# mcu_board.net
KiCad netlist of a schematic drawn in EAGLE
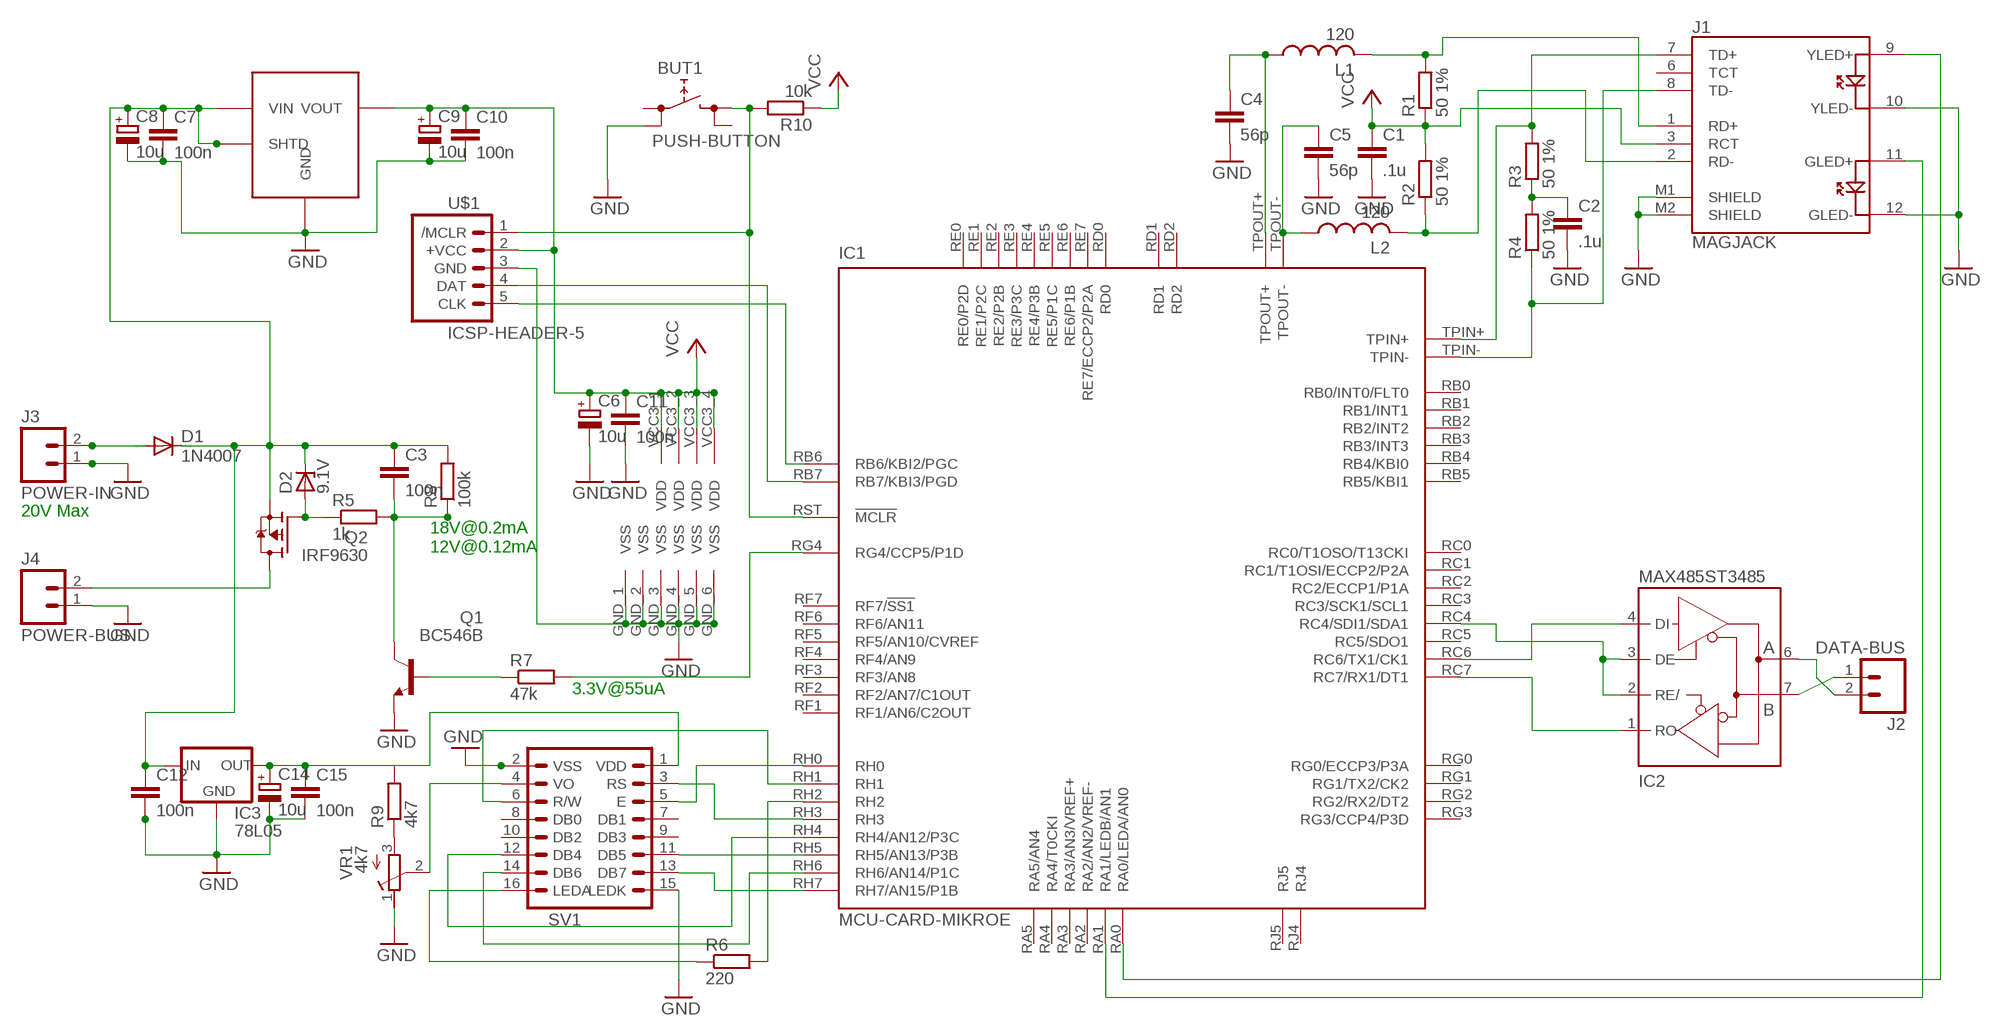
[diagram p0: schematic, sheet 1]

(export (version "E")
  (design (tool "Eeschema 10.0.6"))
  (components
    (comp (ref "BUT1")
      (value "PUSH-BUTTON")
      (footprint "eagle-import:MICRO-SWITCH")
      (libsource (lib "eagle-import") (part "PUSH-BUTTON"))
    )
    (comp (ref "C1")
      (value ".1u")
      (footprint "eagle-import:C050-025X075")
      (libsource (lib "eagle-import") (part "C-EU050-025X075"))
    )
    (comp (ref "C2")
      (value ".1u")
      (footprint "eagle-import:C050-025X075")
      (libsource (lib "eagle-import") (part "C-EU050-025X075"))
    )
    (comp (ref "C3")
      (value "100n")
      (footprint "eagle-import:C050-025X075")
      (libsource (lib "eagle-import") (part "C-EU050-025X075"))
    )
    (comp (ref "C4")
      (value "56p")
      (footprint "eagle-import:C0805")
      (libsource (lib "eagle-import") (part "C-EUC0805"))
    )
    (comp (ref "C5")
      (value "56p")
      (footprint "eagle-import:C0805")
      (libsource (lib "eagle-import") (part "C-EUC0805"))
    )
    (comp (ref "C6")
      (value "10u")
      (footprint "eagle-import:E2,5-6")
      (libsource (lib "eagle-import") (part "CPOL-EUE2.5-6"))
    )
    (comp (ref "C7")
      (value "100n")
      (footprint "eagle-import:C050-025X075")
      (libsource (lib "eagle-import") (part "C-EU050-025X075"))
    )
    (comp (ref "C8")
      (value "10u")
      (footprint "eagle-import:E2,5-7")
      (libsource (lib "eagle-import") (part "CPOL-EUE2.5-7"))
    )
    (comp (ref "C9")
      (value "10u")
      (footprint "eagle-import:E2,5-7")
      (libsource (lib "eagle-import") (part "CPOL-EUE2.5-7"))
    )
    (comp (ref "C10")
      (value "100n")
      (footprint "eagle-import:C050-025X075")
      (libsource (lib "eagle-import") (part "C-EU050-025X075"))
    )
    (comp (ref "C11")
      (value "100n")
      (footprint "eagle-import:C050-025X075")
      (libsource (lib "eagle-import") (part "C-EU050-025X075"))
    )
    (comp (ref "C12")
      (value "100n")
      (footprint "eagle-import:C050-025X075")
      (libsource (lib "eagle-import") (part "C-EU050-025X075"))
    )
    (comp (ref "C14")
      (value "10u")
      (footprint "eagle-import:E2,5-7")
      (libsource (lib "eagle-import") (part "CPOL-EUE2.5-7"))
    )
    (comp (ref "C15")
      (value "100n")
      (footprint "eagle-import:C050-025X075")
      (libsource (lib "eagle-import") (part "C-EU050-025X075"))
    )
    (comp (ref "D1")
      (value "1N4007")
      (footprint "eagle-import:DO41-10")
      (libsource (lib "eagle-import") (part "1N4007"))
    )
    (comp (ref "D2")
      (value "9.1V")
      (footprint "eagle-import:D-5")
      (libsource (lib "eagle-import") (part "ZENERD5"))
    )
    (comp (ref "IC1")
      (value "MCU-CARD-MIKROE")
      (footprint "eagle-import:LV18F")
      (libsource (lib "eagle-import") (part "MCU-CARD-MIKROE"))
    )
    (comp (ref "IC2")
      (value "MAX485ST3485")
      (footprint "eagle-import:SO08")
      (libsource (lib "eagle-import") (part "MAX485ST3485"))
    )
    (comp (ref "IC3")
      (value "78L05")
      (footprint "eagle-import:78LXX")
      (libsource (lib "eagle-import") (part "78LXX"))
    )
    (comp (ref "J1")
      (value "MAGJACK")
      (footprint "eagle-import:MAGJACK")
      (libsource (lib "eagle-import") (part "MAGJACK"))
    )
    (comp (ref "J2")
      (value "DATA-BUS")
      (footprint "eagle-import:SCREWTERMINAL-3.5MM-2")
      (libsource (lib "eagle-import") (part "M02-SCREW-3.5MM3.5MM"))
    )
    (comp (ref "J3")
      (value "POWER-IN")
      (footprint "eagle-import:SCREWTERMINAL-3.5MM-2")
      (libsource (lib "eagle-import") (part "M02-SCREW-3.5MM3.5MM"))
    )
    (comp (ref "J4")
      (value "POWER-BUS")
      (footprint "eagle-import:SCREWTERMINAL-3.5MM-2")
      (libsource (lib "eagle-import") (part "M02-SCREW-3.5MM3.5MM"))
    )
    (comp (ref "L1")
      (value "120")
      (footprint "eagle-import:R0603")
      (libsource (lib "eagle-import") (part "L-US"))
    )
    (comp (ref "L2")
      (value "120")
      (footprint "eagle-import:R0603")
      (libsource (lib "eagle-import") (part "L-US"))
    )
    (comp (ref "Q1")
      (value "BC546B")
      (footprint "eagle-import:TO92-")
      (libsource (lib "eagle-import") (part "BC546B"))
    )
    (comp (ref "Q2")
      (value "IRF9630")
      (footprint "eagle-import:TO220V")
      (libsource (lib "eagle-import") (part "IRF9630"))
    )
    (comp (ref "R1")
      (value "50 1%")
      (footprint "eagle-import:0207_10")
      (libsource (lib "eagle-import") (part "R-EU_0207/10"))
    )
    (comp (ref "R2")
      (value "50 1%")
      (footprint "eagle-import:0207_10")
      (libsource (lib "eagle-import") (part "R-EU_0207/10"))
    )
    (comp (ref "R3")
      (value "50 1%")
      (footprint "eagle-import:0207_10")
      (libsource (lib "eagle-import") (part "R-EU_0207/10"))
    )
    (comp (ref "R4")
      (value "50 1%")
      (footprint "eagle-import:0207_10")
      (libsource (lib "eagle-import") (part "R-EU_0207/10"))
    )
    (comp (ref "R5")
      (value "1k")
      (footprint "eagle-import:0207_10")
      (libsource (lib "eagle-import") (part "R-EU_0207/10"))
    )
    (comp (ref "R6")
      (value "220")
      (footprint "eagle-import:0207_10")
      (libsource (lib "eagle-import") (part "R-EU_0207/10"))
    )
    (comp (ref "R7")
      (value "47k")
      (footprint "eagle-import:0207_10")
      (libsource (lib "eagle-import") (part "R-EU_0207/10"))
    )
    (comp (ref "R8")
      (value "100k")
      (footprint "eagle-import:0207_10")
      (libsource (lib "eagle-import") (part "R-EU_0207/10"))
    )
    (comp (ref "R9")
      (value "4k7")
      (footprint "eagle-import:0207_10")
      (libsource (lib "eagle-import") (part "R-EU_0207/10"))
    )
    (comp (ref "R10")
      (value "10k")
      (footprint "eagle-import:0207_10")
      (libsource (lib "eagle-import") (part "R-EU_0207/10"))
    )
    (comp (ref "SV1")
      (value "WM-C2002M-DISP")
      (footprint "eagle-import:MA08-2")
      (libsource (lib "eagle-import") (part "WM-C2002M-DISP"))
    )
    (comp (ref "U$1")
      (value "ICSP-HEADER-5")
      (footprint "eagle-import:1X05")
      (libsource (lib "eagle-import") (part "ICSP-HEADER-5"))
    )
    (comp (ref "U$3")
      (value "POLOLU-2098")
      (footprint "eagle-import:POLOLU-10-13")
      (libsource (lib "eagle-import") (part "POLOLU-2098"))
    )
    (comp (ref "VR1")
      (value "4k7")
      (footprint "eagle-import:V_TRIMMER")
      (libsource (lib "eagle-import") (part "TRIMMER"))
    )
  )
  (nets
    (net (code "1") (name "GND") (class "Default")
      (node (ref "BUT1") (pin "2") (pinfunction "0_2") (pintype "passive"))
      (node (ref "C1") (pin "2") (pinfunction "2_2") (pintype "passive"))
      (node (ref "C10") (pin "2") (pinfunction "2_2") (pintype "passive"))
      (node (ref "C11") (pin "2") (pinfunction "2_2") (pintype "passive"))
      (node (ref "C12") (pin "2") (pinfunction "2_2") (pintype "passive"))
      (node (ref "C14") (pin "-") (pinfunction "-_-") (pintype "passive"))
      (node (ref "C15") (pin "2") (pinfunction "2_2") (pintype "passive"))
      (node (ref "C2") (pin "2") (pinfunction "2_2") (pintype "passive"))
      (node (ref "C4") (pin "2") (pinfunction "2_2") (pintype "passive"))
      (node (ref "C5") (pin "2") (pinfunction "2_2") (pintype "passive"))
      (node (ref "C6") (pin "-") (pinfunction "-_-") (pintype "passive"))
      (node (ref "C7") (pin "2") (pinfunction "2_2") (pintype "passive"))
      (node (ref "C8") (pin "-") (pinfunction "-_-") (pintype "passive"))
      (node (ref "C9") (pin "-") (pinfunction "-_-") (pintype "passive"))
      (node (ref "IC1") (pin "GND_1") (pinfunction "VSS_GND_1") (pintype "power_in"))
      (node (ref "IC1") (pin "GND_2") (pinfunction "VSS_GND_2") (pintype "power_in"))
      (node (ref "IC1") (pin "GND_3") (pinfunction "VSS_GND_3") (pintype "power_in"))
      (node (ref "IC1") (pin "GND_4") (pinfunction "VSS_GND_4") (pintype "power_in"))
      (node (ref "IC1") (pin "GND_5") (pinfunction "VSS_GND_5") (pintype "power_in"))
      (node (ref "IC1") (pin "GND_6") (pinfunction "VSS_GND_6") (pintype "power_in"))
      (node (ref "IC3") (pin "GND") (pinfunction "GND_GND") (pintype "input"))
      (node (ref "J1") (pin "10") (pinfunction "YLED-_10") (pintype "bidirectional"))
      (node (ref "J1") (pin "12") (pinfunction "GLED-_12") (pintype "bidirectional"))
      (node (ref "J1") (pin "M1") (pinfunction "SHIELD_M1") (pintype "bidirectional"))
      (node (ref "J1") (pin "M2") (pinfunction "SHIELD_M2") (pintype "bidirectional"))
      (node (ref "J3") (pin "1") (pinfunction "1_1") (pintype "passive"))
      (node (ref "J4") (pin "1") (pinfunction "1_1") (pintype "passive"))
      (node (ref "Q1") (pin "1") (pinfunction "E_1") (pintype "passive"))
      (node (ref "SV1") (pin "15") (pinfunction "LEDK_15") (pintype "passive"))
      (node (ref "SV1") (pin "2") (pinfunction "VSS_2") (pintype "passive"))
      (node (ref "U$1") (pin "3") (pinfunction "GND_3") (pintype "passive"))
      (node (ref "U$3") (pin "P$3") (pinfunction "GND_P$3") (pintype "bidirectional"))
      (node (ref "VR1") (pin "1") (pinfunction "A_1") (pintype "passive"))
    )
    (net (code "2") (name "Net-(C2-Pad1)") (class "Default")
      (node (ref "C2") (pin "1") (pinfunction "1_1") (pintype "passive"))
      (node (ref "R3") (pin "1") (pinfunction "1_1") (pintype "passive"))
      (node (ref "R4") (pin "2") (pinfunction "2_2") (pintype "passive"))
    )
    (net (code "3") (name "Net-(C4-Pad1)") (class "Default")
      (node (ref "C4") (pin "1") (pinfunction "1_1") (pintype "passive"))
      (node (ref "IC1") (pin "TPOUT+") (pinfunction "TPOUT+_TPOUT+") (pintype "output"))
      (node (ref "L1") (pin "1") (pinfunction "1_1") (pintype "passive"))
    )
    (net (code "4") (name "Net-(C5-Pad1)") (class "Default")
      (node (ref "C5") (pin "1") (pinfunction "1_1") (pintype "passive"))
      (node (ref "IC1") (pin "TPOUT-") (pinfunction "TPOUT-_TPOUT-") (pintype "output"))
      (node (ref "L2") (pin "1") (pinfunction "1_1") (pintype "passive"))
    )
    (net (code "5") (name "Net-(D1-PadA)") (class "Default")
      (node (ref "D1") (pin "A") (pinfunction "A_A") (pintype "passive"))
      (node (ref "J3") (pin "2") (pinfunction "2_2") (pintype "passive"))
    )
    (net (code "6") (name "Net-(IC1-PadRH2)") (class "Default")
      (node (ref "IC1") (pin "RH2") (pinfunction "RH2_RH2") (pintype "bidirectional"))
      (node (ref "R6") (pin "2") (pinfunction "2_2") (pintype "passive"))
    )
    (net (code "7") (name "Net-(IC1-RA0{slash}LEDA{slash}AN0)") (class "Default")
      (node (ref "IC1") (pin "RA0") (pinfunction "RA0/LEDA/AN0_RA0") (pintype "bidirectional"))
      (node (ref "J1") (pin "9") (pinfunction "YLED+_9") (pintype "bidirectional"))
    )
    (net (code "8") (name "Net-(IC1-RA1{slash}LEDB{slash}AN1)") (class "Default")
      (node (ref "IC1") (pin "RA1") (pinfunction "RA1/LEDB/AN1_RA1") (pintype "bidirectional"))
      (node (ref "J1") (pin "11") (pinfunction "GLED+_11") (pintype "bidirectional"))
    )
    (net (code "9") (name "Net-(IC1-RB6{slash}KBI2{slash}PGC)") (class "Default")
      (node (ref "IC1") (pin "RB6") (pinfunction "RB6/KBI2/PGC_RB6") (pintype "bidirectional"))
      (node (ref "U$1") (pin "5") (pinfunction "CLK_5") (pintype "passive"))
    )
    (net (code "10") (name "Net-(IC1-RB7{slash}KBI3{slash}PGD)") (class "Default")
      (node (ref "IC1") (pin "RB7") (pinfunction "RB7/KBI3/PGD_RB7") (pintype "bidirectional"))
      (node (ref "U$1") (pin "4") (pinfunction "DAT_4") (pintype "passive"))
    )
    (net (code "11") (name "Net-(IC1-RC4{slash}SDI1{slash}SDA1)") (class "Default")
      (node (ref "IC1") (pin "RC4") (pinfunction "RC4/SDI1/SDA1_RC4") (pintype "bidirectional"))
      (node (ref "IC2") (pin "2") (pinfunction "RE/_2") (pintype "input"))
      (node (ref "IC2") (pin "3") (pinfunction "DE_3") (pintype "input"))
    )
    (net (code "12") (name "Net-(IC1-RC6{slash}TX1{slash}CK1)") (class "Default")
      (node (ref "IC1") (pin "RC6") (pinfunction "RC6/TX1/CK1_RC6") (pintype "bidirectional"))
      (node (ref "IC2") (pin "4") (pinfunction "DI_4") (pintype "input"))
    )
    (net (code "13") (name "Net-(IC1-RC7{slash}RX1{slash}DT1)") (class "Default")
      (node (ref "IC1") (pin "RC7") (pinfunction "RC7/RX1/DT1_RC7") (pintype "bidirectional"))
      (node (ref "IC2") (pin "1") (pinfunction "RO_1") (pintype "output"))
    )
    (net (code "14") (name "Net-(IC1-RG4{slash}CCP5{slash}P1D)") (class "Default")
      (node (ref "IC1") (pin "RG4") (pinfunction "RG4/CCP5/P1D_RG4") (pintype "bidirectional"))
      (node (ref "R7") (pin "2") (pinfunction "2_2") (pintype "passive"))
    )
    (net (code "15") (name "Net-(IC1-RH4{slash}AN12{slash}P3C)") (class "Default")
      (node (ref "IC1") (pin "RH4") (pinfunction "RH4/AN12/P3C_RH4") (pintype "bidirectional"))
      (node (ref "SV1") (pin "12") (pinfunction "DB4_12") (pintype "passive"))
    )
    (net (code "16") (name "Net-(IC1-RH5{slash}AN13{slash}P3B)") (class "Default")
      (node (ref "IC1") (pin "RH5") (pinfunction "RH5/AN13/P3B_RH5") (pintype "bidirectional"))
      (node (ref "SV1") (pin "11") (pinfunction "DB5_11") (pintype "passive"))
    )
    (net (code "17") (name "Net-(IC1-RH6{slash}AN14{slash}P1C)") (class "Default")
      (node (ref "IC1") (pin "RH6") (pinfunction "RH6/AN14/P1C_RH6") (pintype "bidirectional"))
      (node (ref "SV1") (pin "14") (pinfunction "DB6_14") (pintype "passive"))
    )
    (net (code "18") (name "Net-(IC1-RH7{slash}AN15{slash}P1B)") (class "Default")
      (node (ref "IC1") (pin "RH7") (pinfunction "RH7/AN15/P1B_RH7") (pintype "bidirectional"))
      (node (ref "SV1") (pin "13") (pinfunction "DB7_13") (pintype "passive"))
    )
    (net (code "19") (name "Net-(IC1-~{MCLR})") (class "Default")
      (node (ref "BUT1") (pin "3") (pinfunction "1_3") (pintype "passive"))
      (node (ref "IC1") (pin "RST") (pinfunction "~{MCLR}_RST") (pintype "input"))
      (node (ref "R10") (pin "2") (pinfunction "2_2") (pintype "passive"))
      (node (ref "U$1") (pin "1") (pinfunction "/MCLR_1") (pintype "passive"))
    )
    (net (code "20") (name "Net-(IC2A-A)") (class "Default")
      (node (ref "IC2") (pin "6") (pinfunction "A_6") (pintype "passive"))
      (node (ref "J2") (pin "2") (pinfunction "2_2") (pintype "passive"))
    )
    (net (code "21") (name "Net-(IC2A-B)") (class "Default")
      (node (ref "IC2") (pin "7") (pinfunction "B_7") (pintype "passive"))
      (node (ref "J2") (pin "1") (pinfunction "1_1") (pintype "passive"))
    )
    (net (code "22") (name "Net-(J1-RD+)") (class "Default")
      (node (ref "J1") (pin "1") (pinfunction "RD+_1") (pintype "bidirectional"))
      (node (ref "L1") (pin "2") (pinfunction "2_2") (pintype "passive"))
      (node (ref "R1") (pin "2") (pinfunction "2_2") (pintype "passive"))
    )
    (net (code "23") (name "Net-(J1-RD-)") (class "Default")
      (node (ref "J1") (pin "2") (pinfunction "RD-_2") (pintype "bidirectional"))
      (node (ref "L2") (pin "2") (pinfunction "2_2") (pintype "passive"))
      (node (ref "R2") (pin "1") (pinfunction "1_1") (pintype "passive"))
    )
    (net (code "24") (name "Net-(J1-TD+)") (class "Default")
      (node (ref "IC1") (pin "TPIN+") (pinfunction "TPIN+_TPIN+") (pintype "input"))
      (node (ref "J1") (pin "7") (pinfunction "TD+_7") (pintype "bidirectional"))
      (node (ref "R3") (pin "2") (pinfunction "2_2") (pintype "passive"))
    )
    (net (code "25") (name "Net-(J1-TD-)") (class "Default")
      (node (ref "IC1") (pin "TPIN-") (pinfunction "TPIN-_TPIN-") (pintype "input"))
      (node (ref "J1") (pin "8") (pinfunction "TD-_8") (pintype "bidirectional"))
      (node (ref "R4") (pin "1") (pinfunction "1_1") (pintype "passive"))
    )
    (net (code "26") (name "Net-(Q1-B)") (class "Default")
      (node (ref "Q1") (pin "2") (pinfunction "B_2") (pintype "passive"))
      (node (ref "R7") (pin "1") (pinfunction "1_1") (pintype "passive"))
    )
    (net (code "27") (name "Net-(Q1-C)") (class "Default")
      (node (ref "C3") (pin "2") (pinfunction "2_2") (pintype "passive"))
      (node (ref "Q1") (pin "3") (pinfunction "C_3") (pintype "passive"))
      (node (ref "R5") (pin "2") (pinfunction "2_2") (pintype "passive"))
      (node (ref "R8") (pin "1") (pinfunction "1_1") (pintype "passive"))
    )
    (net (code "28") (name "Net-(Q2-D)") (class "Default")
      (node (ref "J4") (pin "2") (pinfunction "2_2") (pintype "passive"))
      (node (ref "Q2") (pin "2") (pinfunction "D_2") (pintype "passive"))
    )
    (net (code "29") (name "Net-(Q2-G)") (class "Default")
      (node (ref "D2") (pin "A") (pinfunction "A_A") (pintype "passive"))
      (node (ref "Q2") (pin "1") (pinfunction "G_1") (pintype "passive"))
      (node (ref "R5") (pin "1") (pinfunction "1_1") (pintype "passive"))
    )
    (net (code "30") (name "Net-(Q2-S)") (class "Default")
      (node (ref "C12") (pin "1") (pinfunction "1_1") (pintype "passive"))
      (node (ref "C3") (pin "1") (pinfunction "1_1") (pintype "passive"))
      (node (ref "C7") (pin "1") (pinfunction "1_1") (pintype "passive"))
      (node (ref "C8") (pin "+") (pinfunction "+_+") (pintype "passive"))
      (node (ref "D1") (pin "C") (pinfunction "C_C") (pintype "passive"))
      (node (ref "D2") (pin "C") (pinfunction "C_C") (pintype "passive"))
      (node (ref "IC3") (pin "IN") (pinfunction "IN_IN") (pintype "input"))
      (node (ref "Q2") (pin "3") (pinfunction "S_3") (pintype "passive"))
      (node (ref "R8") (pin "2") (pinfunction "2_2") (pintype "passive"))
      (node (ref "U$3") (pin "P$1") (pinfunction "SHTD_P$1") (pintype "power_in"))
      (node (ref "U$3") (pin "P$2") (pinfunction "VIN_P$2") (pintype "power_in"))
    )
    (net (code "31") (name "Net-(SV1-E)") (class "Default")
      (node (ref "IC1") (pin "RH0") (pinfunction "RH0_RH0") (pintype "bidirectional"))
      (node (ref "SV1") (pin "5") (pinfunction "E_5") (pintype "passive"))
    )
    (net (code "32") (name "Net-(SV1-LEDA)") (class "Default")
      (node (ref "R6") (pin "1") (pinfunction "1_1") (pintype "passive"))
      (node (ref "SV1") (pin "16") (pinfunction "LEDA_16") (pintype "passive"))
    )
    (net (code "33") (name "Net-(SV1-RS)") (class "Default")
      (node (ref "IC1") (pin "RH3") (pinfunction "RH3_RH3") (pintype "bidirectional"))
      (node (ref "SV1") (pin "3") (pinfunction "RS_3") (pintype "passive"))
    )
    (net (code "34") (name "Net-(SV1-R{slash}W)") (class "Default")
      (node (ref "IC1") (pin "RH1") (pinfunction "RH1_RH1") (pintype "bidirectional"))
      (node (ref "SV1") (pin "6") (pinfunction "R/W_6") (pintype "passive"))
    )
    (net (code "35") (name "Net-(SV1-VDD)") (class "Default")
      (node (ref "C14") (pin "+") (pinfunction "+_+") (pintype "passive"))
      (node (ref "C15") (pin "1") (pinfunction "1_1") (pintype "passive"))
      (node (ref "IC3") (pin "OUT") (pinfunction "OUT_OUT") (pintype "passive"))
      (node (ref "R9") (pin "2") (pinfunction "2_2") (pintype "passive"))
      (node (ref "SV1") (pin "1") (pinfunction "VDD_1") (pintype "passive"))
    )
    (net (code "36") (name "Net-(SV1-VO)") (class "Default")
      (node (ref "SV1") (pin "4") (pinfunction "VO_4") (pintype "passive"))
      (node (ref "VR1") (pin "2") (pinfunction "S_2") (pintype "passive"))
    )
    (net (code "37") (name "Net-(VR1-E)") (class "Default")
      (node (ref "R9") (pin "1") (pinfunction "1_1") (pintype "passive"))
      (node (ref "VR1") (pin "3") (pinfunction "E_3") (pintype "passive"))
    )
    (net (code "38") (name "VCC") (class "Default")
      (node (ref "C1") (pin "1") (pinfunction "1_1") (pintype "passive"))
      (node (ref "C10") (pin "1") (pinfunction "1_1") (pintype "passive"))
      (node (ref "C11") (pin "1") (pinfunction "1_1") (pintype "passive"))
      (node (ref "C6") (pin "+") (pinfunction "+_+") (pintype "passive"))
      (node (ref "C9") (pin "+") (pinfunction "+_+") (pintype "passive"))
      (node (ref "IC1") (pin "VCC3_1") (pinfunction "VDD_VCC3_1") (pintype "power_in"))
      (node (ref "IC1") (pin "VCC3_2") (pinfunction "VDD_VCC3_2") (pintype "power_in"))
      (node (ref "IC1") (pin "VCC3_3") (pinfunction "VDD_VCC3_3") (pintype "power_in"))
      (node (ref "IC1") (pin "VCC3_4") (pinfunction "VDD_VCC3_4") (pintype "power_in"))
      (node (ref "J1") (pin "3") (pinfunction "RCT_3") (pintype "bidirectional"))
      (node (ref "R1") (pin "1") (pinfunction "1_1") (pintype "passive"))
      (node (ref "R10") (pin "1") (pinfunction "1_1") (pintype "passive"))
      (node (ref "R2") (pin "2") (pinfunction "2_2") (pintype "passive"))
      (node (ref "U$1") (pin "2") (pinfunction "+VCC_2") (pintype "passive"))
      (node (ref "U$3") (pin "P$4") (pinfunction "VOUT_P$4") (pintype "bidirectional"))
    )
    (net (code "39") (name "unconnected-(BUT1-0-Pad1)") (class "Default")
      (node (ref "BUT1") (pin "1") (pinfunction "0_1") (pintype "passive"))
    )
    (net (code "40") (name "unconnected-(BUT1-1-Pad4)") (class "Default")
      (node (ref "BUT1") (pin "4") (pinfunction "1_4") (pintype "passive"))
    )
    (net (code "41") (name "unconnected-(IC1-PadRD0)") (class "Default")
      (node (ref "IC1") (pin "RD0") (pinfunction "RD0_RD0") (pintype "bidirectional"))
    )
    (net (code "42") (name "unconnected-(IC1-PadRD1)") (class "Default")
      (node (ref "IC1") (pin "RD1") (pinfunction "RD1_RD1") (pintype "bidirectional"))
    )
    (net (code "43") (name "unconnected-(IC1-PadRD2)") (class "Default")
      (node (ref "IC1") (pin "RD2") (pinfunction "RD2_RD2") (pintype "bidirectional"))
    )
    (net (code "44") (name "unconnected-(IC1-PadRJ4)") (class "Default")
      (node (ref "IC1") (pin "RJ4") (pinfunction "RJ4_RJ4") (pintype "bidirectional"))
    )
    (net (code "45") (name "unconnected-(IC1-PadRJ5)") (class "Default")
      (node (ref "IC1") (pin "RJ5") (pinfunction "RJ5_RJ5") (pintype "bidirectional"))
    )
    (net (code "46") (name "unconnected-(IC1-RA2{slash}AN2{slash}VREF--PadRA2)") (class "Default")
      (node (ref "IC1") (pin "RA2") (pinfunction "RA2/AN2/VREF-_RA2") (pintype "bidirectional"))
    )
    (net (code "47") (name "unconnected-(IC1-RA3{slash}AN3{slash}VREF+-PadRA3)") (class "Default")
      (node (ref "IC1") (pin "RA3") (pinfunction "RA3/AN3/VREF+_RA3") (pintype "bidirectional"))
    )
    (net (code "48") (name "unconnected-(IC1-RA4{slash}T0CKI-PadRA4)") (class "Default")
      (node (ref "IC1") (pin "RA4") (pinfunction "RA4/T0CKI_RA4") (pintype "bidirectional"))
    )
    (net (code "49") (name "unconnected-(IC1-RA5{slash}AN4-PadRA5)") (class "Default")
      (node (ref "IC1") (pin "RA5") (pinfunction "RA5/AN4_RA5") (pintype "bidirectional"))
    )
    (net (code "50") (name "unconnected-(IC1-RB0{slash}INT0{slash}FLT0-PadRB0)") (class "Default")
      (node (ref "IC1") (pin "RB0") (pinfunction "RB0/INT0/FLT0_RB0") (pintype "bidirectional"))
    )
    (net (code "51") (name "unconnected-(IC1-RB1{slash}INT1-PadRB1)") (class "Default")
      (node (ref "IC1") (pin "RB1") (pinfunction "RB1/INT1_RB1") (pintype "bidirectional"))
    )
    (net (code "52") (name "unconnected-(IC1-RB2{slash}INT2-PadRB2)") (class "Default")
      (node (ref "IC1") (pin "RB2") (pinfunction "RB2/INT2_RB2") (pintype "bidirectional"))
    )
    (net (code "53") (name "unconnected-(IC1-RB3{slash}INT3-PadRB3)") (class "Default")
      (node (ref "IC1") (pin "RB3") (pinfunction "RB3/INT3_RB3") (pintype "bidirectional"))
    )
    (net (code "54") (name "unconnected-(IC1-RB4{slash}KBI0-PadRB4)") (class "Default")
      (node (ref "IC1") (pin "RB4") (pinfunction "RB4/KBI0_RB4") (pintype "bidirectional"))
    )
    (net (code "55") (name "unconnected-(IC1-RB5{slash}KBI1-PadRB5)") (class "Default")
      (node (ref "IC1") (pin "RB5") (pinfunction "RB5/KBI1_RB5") (pintype "bidirectional"))
    )
    (net (code "56") (name "unconnected-(IC1-RC0{slash}T1OSO{slash}T13CKI-PadRC0)") (class "Default")
      (node (ref "IC1") (pin "RC0") (pinfunction "RC0/T1OSO/T13CKI_RC0") (pintype "bidirectional"))
    )
    (net (code "57") (name "unconnected-(IC1-RC1{slash}T1OSI{slash}ECCP2{slash}P2A-PadRC1)") (class "Default")
      (node (ref "IC1") (pin "RC1") (pinfunction "RC1/T1OSI/ECCP2/P2A_RC1") (pintype "bidirectional"))
    )
    (net (code "58") (name "unconnected-(IC1-RC2{slash}ECCP1{slash}P1A-PadRC2)") (class "Default")
      (node (ref "IC1") (pin "RC2") (pinfunction "RC2/ECCP1/P1A_RC2") (pintype "bidirectional"))
    )
    (net (code "59") (name "unconnected-(IC1-RC3{slash}SCK1{slash}SCL1-PadRC3)") (class "Default")
      (node (ref "IC1") (pin "RC3") (pinfunction "RC3/SCK1/SCL1_RC3") (pintype "bidirectional"))
    )
    (net (code "60") (name "unconnected-(IC1-RC5{slash}SDO1-PadRC5)") (class "Default")
      (node (ref "IC1") (pin "RC5") (pinfunction "RC5/SDO1_RC5") (pintype "bidirectional"))
    )
    (net (code "61") (name "unconnected-(IC1-RE0{slash}P2D-PadRE0)") (class "Default")
      (node (ref "IC1") (pin "RE0") (pinfunction "RE0/P2D_RE0") (pintype "bidirectional"))
    )
    (net (code "62") (name "unconnected-(IC1-RE1{slash}P2C-PadRE1)") (class "Default")
      (node (ref "IC1") (pin "RE1") (pinfunction "RE1/P2C_RE1") (pintype "bidirectional"))
    )
    (net (code "63") (name "unconnected-(IC1-RE2{slash}P2B-PadRE2)") (class "Default")
      (node (ref "IC1") (pin "RE2") (pinfunction "RE2/P2B_RE2") (pintype "bidirectional"))
    )
    (net (code "64") (name "unconnected-(IC1-RE3{slash}P3C-PadRE3)") (class "Default")
      (node (ref "IC1") (pin "RE3") (pinfunction "RE3/P3C_RE3") (pintype "bidirectional"))
    )
    (net (code "65") (name "unconnected-(IC1-RE4{slash}P3B-PadRE4)") (class "Default")
      (node (ref "IC1") (pin "RE4") (pinfunction "RE4/P3B_RE4") (pintype "bidirectional"))
    )
    (net (code "66") (name "unconnected-(IC1-RE5{slash}P1C-PadRE5)") (class "Default")
      (node (ref "IC1") (pin "RE5") (pinfunction "RE5/P1C_RE5") (pintype "bidirectional"))
    )
    (net (code "67") (name "unconnected-(IC1-RE6{slash}P1B-PadRE6)") (class "Default")
      (node (ref "IC1") (pin "RE6") (pinfunction "RE6/P1B_RE6") (pintype "bidirectional"))
    )
    (net (code "68") (name "unconnected-(IC1-RE7{slash}ECCP2{slash}P2A-PadRE7)") (class "Default")
      (node (ref "IC1") (pin "RE7") (pinfunction "RE7/ECCP2/P2A_RE7") (pintype "bidirectional"))
    )
    (net (code "69") (name "unconnected-(IC1-RF1{slash}AN6{slash}C2OUT-PadRF1)") (class "Default")
      (node (ref "IC1") (pin "RF1") (pinfunction "RF1/AN6/C2OUT_RF1") (pintype "bidirectional"))
    )
    (net (code "70") (name "unconnected-(IC1-RF2{slash}AN7{slash}C1OUT-PadRF2)") (class "Default")
      (node (ref "IC1") (pin "RF2") (pinfunction "RF2/AN7/C1OUT_RF2") (pintype "bidirectional"))
    )
    (net (code "71") (name "unconnected-(IC1-RF3{slash}AN8-PadRF3)") (class "Default")
      (node (ref "IC1") (pin "RF3") (pinfunction "RF3/AN8_RF3") (pintype "bidirectional"))
    )
    (net (code "72") (name "unconnected-(IC1-RF4{slash}AN9-PadRF4)") (class "Default")
      (node (ref "IC1") (pin "RF4") (pinfunction "RF4/AN9_RF4") (pintype "bidirectional"))
    )
    (net (code "73") (name "unconnected-(IC1-RF5{slash}AN10{slash}CVREF-PadRF5)") (class "Default")
      (node (ref "IC1") (pin "RF5") (pinfunction "RF5/AN10/CVREF_RF5") (pintype "bidirectional"))
    )
    (net (code "74") (name "unconnected-(IC1-RF6{slash}AN11-PadRF6)") (class "Default")
      (node (ref "IC1") (pin "RF6") (pinfunction "RF6/AN11_RF6") (pintype "bidirectional"))
    )
    (net (code "75") (name "unconnected-(IC1-RF7{slash}~{SS1}-PadRF7)") (class "Default")
      (node (ref "IC1") (pin "RF7") (pinfunction "RF7/~{SS1}_RF7") (pintype "bidirectional"))
    )
    (net (code "76") (name "unconnected-(IC1-RG0{slash}ECCP3{slash}P3A-PadRG0)") (class "Default")
      (node (ref "IC1") (pin "RG0") (pinfunction "RG0/ECCP3/P3A_RG0") (pintype "bidirectional"))
    )
    (net (code "77") (name "unconnected-(IC1-RG1{slash}TX2{slash}CK2-PadRG1)") (class "Default")
      (node (ref "IC1") (pin "RG1") (pinfunction "RG1/TX2/CK2_RG1") (pintype "bidirectional"))
    )
    (net (code "78") (name "unconnected-(IC1-RG2{slash}RX2{slash}DT2-PadRG2)") (class "Default")
      (node (ref "IC1") (pin "RG2") (pinfunction "RG2/RX2/DT2_RG2") (pintype "bidirectional"))
    )
    (net (code "79") (name "unconnected-(IC1-RG3{slash}CCP4{slash}P3D-PadRG3)") (class "Default")
      (node (ref "IC1") (pin "RG3") (pinfunction "RG3/CCP4/P3D_RG3") (pintype "bidirectional"))
    )
    (net (code "80") (name "unconnected-(J1-TCT-Pad6)") (class "Default")
      (node (ref "J1") (pin "6") (pinfunction "TCT_6") (pintype "bidirectional"))
    )
    (net (code "81") (name "unconnected-(SV1-DB0-Pad8)") (class "Default")
      (node (ref "SV1") (pin "8") (pinfunction "DB0_8") (pintype "passive"))
    )
    (net (code "82") (name "unconnected-(SV1-DB1-Pad7)") (class "Default")
      (node (ref "SV1") (pin "7") (pinfunction "DB1_7") (pintype "passive"))
    )
    (net (code "83") (name "unconnected-(SV1-DB2-Pad10)") (class "Default")
      (node (ref "SV1") (pin "10") (pinfunction "DB2_10") (pintype "passive"))
    )
    (net (code "84") (name "unconnected-(SV1-DB3-Pad9)") (class "Default")
      (node (ref "SV1") (pin "9") (pinfunction "DB3_9") (pintype "passive"))
    )
  )
)
